# MASTER.net
KiCad netlist of a schematic drawn in Altium Designer
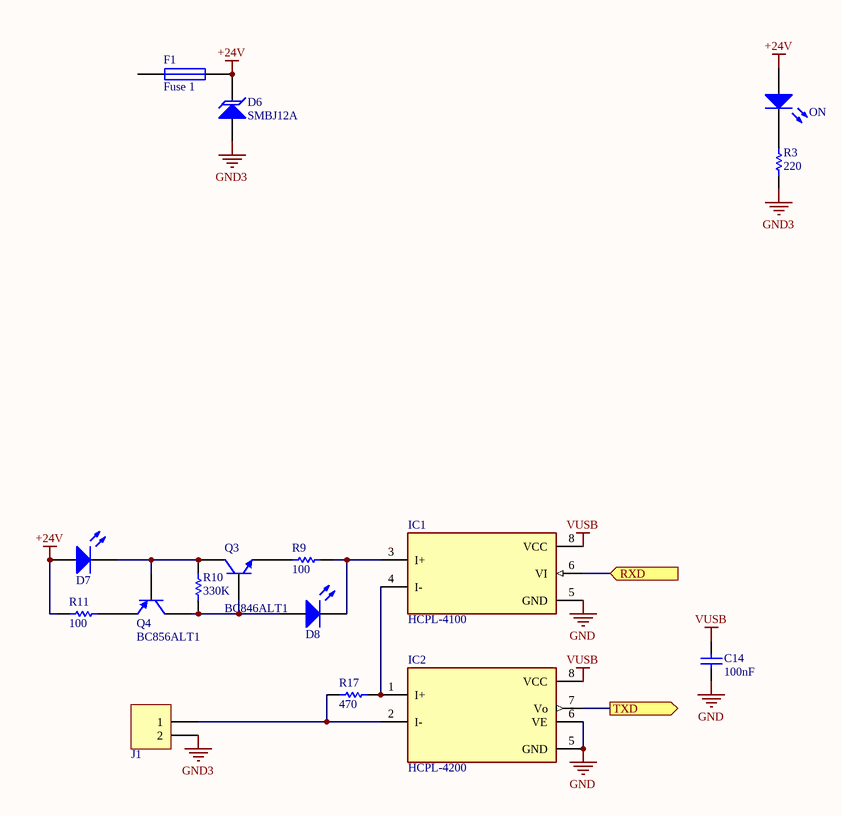
[diagram p0: MASTER.SchDoc]

(export (version "E")
  (design (tool "Eeschema 10.0.6"))
  (components
    (comp (ref "C14")
      (value "100nF")
      (footprint "C603")
      (description "Capacitor")
      (fields (field (name "DESIGNER") "Parsa Malekpour"))
      (libsource (lib "ParsaLibrary") (part "Cap"))
    )
    (comp (ref "D6")
      (value "SMBJ12A")
      (footprint "DO-214AA")
      (description "Surface Mount Transient Voltage Suppressors Diode")
      (libsource (lib "ParsaLibrary") (part "SMBJxxA"))
    )
    (comp (ref "D7") (value "LED") (footprint "LED-1206") (libsource (lib "ParsaLibrary") (part "LED")))
    (comp (ref "D8") (value "LED") (footprint "LED-1206") (libsource (lib "ParsaLibrary") (part "LED")))
    (comp (ref "F1")
      (value "Fuse 1")
      (footprint "PTC-0805")
      (description "Fuse")
      (fields (field (name "PUBLISHER") "Altium Limited"))
      (libsource (lib "Miscellaneous Devices") (part "Fuse 1"))
    )
    (comp (ref "IC1")
      (value "HCPL-4100")
      (footprint "PARSALIBRARY:DIP-8")
      (description "<b>Isolation Amplifer</b><p> Source: http://www.avagotech.com/docs/AV02-0410EN")
      (fields (field (name "MF") "{'manufacturer': u'Broadcom Limited'}"))
      (libsource (lib "ParsaLibrary") (part "HCPL-4100"))
    )
    (comp (ref "IC2")
      (value "HCPL-4200")
      (footprint "PARSALIBRARY:DIP-8")
      (description "Optically Coupled 20 mA Current Loop Receiver")
      (fields (field (name "MF") "{'manufacturer': u'Broadcom Limited'}") (field (name "MP") "HCPL-4100"))
      (libsource (lib "ParsaLibrary") (part "HCPL-4200"))
    )
    (comp (ref "J1") (value "CONN-2") (footprint "XH-2") (libsource (lib "ParsaLibrary") (part "CONN-2")))
    (comp (ref "ON") (value "LED") (footprint "LED-1206") (libsource (lib "ParsaLibrary") (part "LED")))
    (comp (ref "Q3")
      (value "BC846ALT1")
      (footprint "SOT-23")
      (description "General Purpose Transistor NPN Silicon")
      (fields (field (name "PUBLISHER") "Altium Limited"))
      (libsource (lib "Motorola Discrete BJT") (part "BC846ALT1"))
    )
    (comp (ref "Q4")
      (value "BC856ALT1")
      (footprint "SOT-23")
      (description "General Purpose Transistor PNP Silicon")
      (fields (field (name "PUBLISHER") "Altium Limited"))
      (libsource (lib "Motorola Discrete BJT") (part "BC856ALT1"))
    )
    (comp (ref "R3")
      (value "220")
      (footprint "R805")
      (description "Resistor")
      (fields (field (name "DESIGNER") "Parsa Malekpour"))
      (libsource (lib "ParsaLibrary") (part "Resistor"))
    )
    (comp (ref "R9")
      (value "100")
      (footprint "R805")
      (description "Resistor")
      (fields (field (name "DESIGNER") "Parsa Malekpour"))
      (libsource (lib "ParsaLibrary") (part "Resistor"))
    )
    (comp (ref "R10")
      (value "330K")
      (footprint "R805")
      (description "Resistor")
      (fields (field (name "DESIGNER") "Parsa Malekpour"))
      (libsource (lib "ParsaLibrary") (part "Resistor"))
    )
    (comp (ref "R11")
      (value "100")
      (footprint "R805")
      (description "Resistor")
      (fields (field (name "DESIGNER") "Parsa Malekpour"))
      (libsource (lib "ParsaLibrary") (part "Resistor"))
    )
    (comp (ref "R17")
      (value "470")
      (footprint "R805")
      (description "Resistor")
      (fields (field (name "DESIGNER") "Parsa Malekpour"))
      (libsource (lib "ParsaLibrary") (part "Resistor"))
    )
  )
  (nets
    (net (code "1") (name "+24V") (class "Default")
      (node (ref "D6") (pin "2") (pinfunction "K_2") (pintype "passive"))
      (node (ref "D7") (pin "1") (pinfunction "A_1") (pintype "passive"))
      (node (ref "F1") (pin "2") (pinfunction "2_2") (pintype "passive"))
      (node (ref "ON") (pin "1") (pinfunction "A_1") (pintype "passive"))
      (node (ref "R11") (pin "2") (pinfunction "2_2") (pintype "passive"))
    )
    (net (code "2") (name "/RXD") (class "Default")
      (node (ref "IC1") (pin "6") (pinfunction "VI_6") (pintype "input"))
    )
    (net (code "3") (name "/TXD") (class "Default")
      (node (ref "IC2") (pin "7") (pinfunction "Vo_7") (pintype "output"))
    )
    (net (code "4") (name "GND") (class "Default")
      (node (ref "C14") (pin "1") (pinfunction "1_1") (pintype "passive"))
      (node (ref "IC1") (pin "5") (pinfunction "GND_5") (pintype "power_in"))
      (node (ref "IC2") (pin "5") (pinfunction "GND_5") (pintype "power_in"))
      (node (ref "IC2") (pin "6") (pinfunction "VE_6") (pintype "power_in"))
    )
    (net (code "5") (name "GND3") (class "Default")
      (node (ref "D6") (pin "1") (pinfunction "A_1") (pintype "passive"))
      (node (ref "J1") (pin "2") (pinfunction "2_2") (pintype "passive"))
      (node (ref "R3") (pin "1") (pinfunction "1_1") (pintype "passive"))
    )
    (net (code "6") (name "Net-(D7-K)") (class "Default")
      (node (ref "D7") (pin "2") (pinfunction "K_2") (pintype "passive"))
      (node (ref "Q3") (pin "3") (pinfunction "C_3") (pintype "passive"))
      (node (ref "Q4") (pin "1") (pinfunction "B_1") (pintype "passive"))
      (node (ref "R10") (pin "1") (pinfunction "1_1") (pintype "passive"))
    )
    (net (code "7") (name "Net-(D8-A)") (class "Default")
      (node (ref "D8") (pin "1") (pinfunction "A_1") (pintype "passive"))
      (node (ref "Q3") (pin "1") (pinfunction "B_1") (pintype "passive"))
      (node (ref "Q4") (pin "3") (pinfunction "C_3") (pintype "passive"))
      (node (ref "R10") (pin "2") (pinfunction "2_2") (pintype "passive"))
    )
    (net (code "8") (name "Net-(D8-K)") (class "Default")
      (node (ref "D8") (pin "2") (pinfunction "K_2") (pintype "passive"))
      (node (ref "IC1") (pin "3") (pinfunction "I+_3") (pintype "power_in"))
      (node (ref "R9") (pin "1") (pinfunction "1_1") (pintype "passive"))
    )
    (net (code "9") (name "Net-(IC1-I-)") (class "Default")
      (node (ref "IC1") (pin "4") (pinfunction "I-_4") (pintype "power_in"))
      (node (ref "IC2") (pin "1") (pinfunction "I+_1") (pintype "power_in"))
      (node (ref "R17") (pin "2") (pinfunction "2_2") (pintype "passive"))
    )
    (net (code "10") (name "Net-(IC2-I-)") (class "Default")
      (node (ref "IC2") (pin "2") (pinfunction "I-_2") (pintype "power_in"))
      (node (ref "J1") (pin "1") (pinfunction "1_1") (pintype "passive"))
      (node (ref "R17") (pin "1") (pinfunction "1_1") (pintype "passive"))
    )
    (net (code "11") (name "Net-(ON-K)") (class "Default")
      (node (ref "ON") (pin "2") (pinfunction "K_2") (pintype "passive"))
      (node (ref "R3") (pin "2") (pinfunction "2_2") (pintype "passive"))
    )
    (net (code "12") (name "Net-(Q3-E)") (class "Default")
      (node (ref "Q3") (pin "2") (pinfunction "E_2") (pintype "passive"))
      (node (ref "R9") (pin "2") (pinfunction "2_2") (pintype "passive"))
    )
    (net (code "13") (name "Net-(Q4-E)") (class "Default")
      (node (ref "Q4") (pin "2") (pinfunction "E_2") (pintype "passive"))
      (node (ref "R11") (pin "1") (pinfunction "1_1") (pintype "passive"))
    )
    (net (code "14") (name "VUSB") (class "Default")
      (node (ref "C14") (pin "2") (pinfunction "2_2") (pintype "passive"))
      (node (ref "IC1") (pin "8") (pinfunction "VCC_8") (pintype "power_in"))
      (node (ref "IC2") (pin "8") (pinfunction "VCC_8") (pintype "power_in"))
    )
    (net (code "15") (name "unconnected-(F1-Pad1)") (class "Default")
      (node (ref "F1") (pin "1") (pinfunction "1_1") (pintype "passive"))
    )
  )
)
